# Connectors.net
KiCad netlist of a schematic drawn in Altium Designer
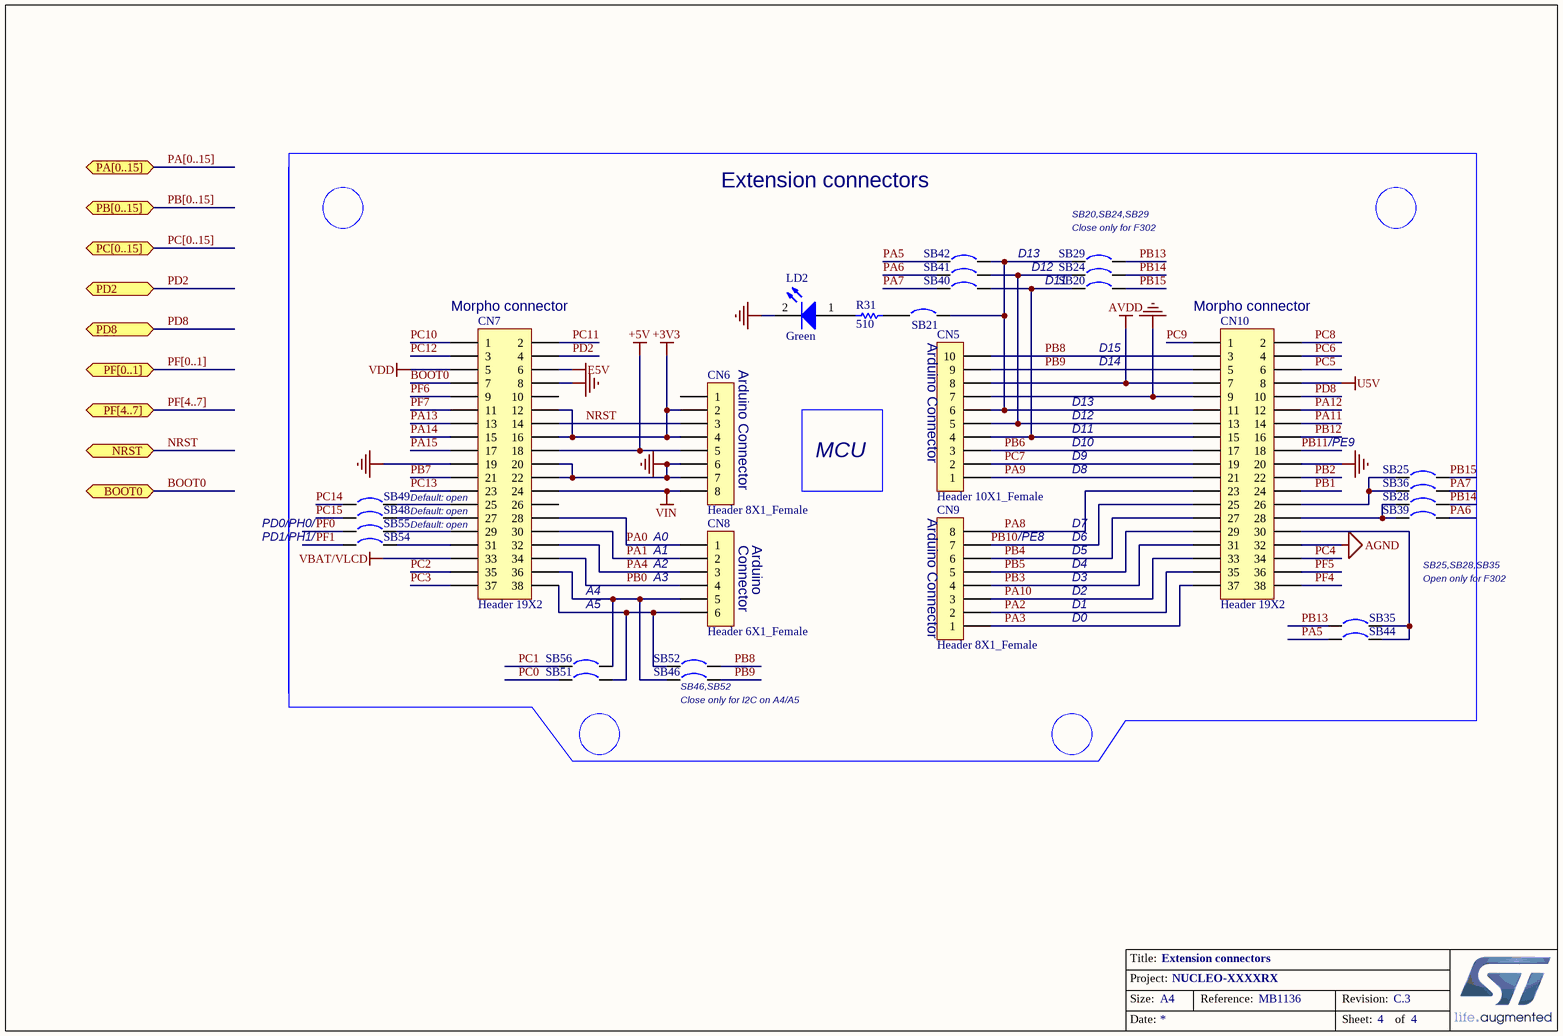
[diagram p0: Connectors.SchDoc]

(export (version "E")
  (design (tool "Eeschema 10.0.6"))
  (components
    (comp (ref "CN5")
      (value "Header 10X1_Female")
      (footprint "1*10P_FEMALE")
      (description "Header, 10-Pin, Single row,female")
      (fields (field (name "PUBLISHER") "Altium Limited"))
      (libsource (lib "Nucleo_64") (part "Header 10X1_Female"))
    )
    (comp (ref "CN6")
      (value "Header 8X1_Female")
      (footprint "1*8P_FEMALE")
      (description "Header, 8-Pin, Single row,female")
      (fields (field (name "PUBLISHER") "Altium Limited"))
      (libsource (lib "") (part "Header 8X1_Female_1"))
    )
    (comp (ref "CN7")
      (value "Header 19X2")
      (footprint "2*19P")
      (description "Header, 19-Pin, Dual row")
      (fields (field (name "PUBLISHER") "Altium Limited"))
      (libsource (lib "Nucleo_64_1") (part "Header 19X2"))
    )
    (comp (ref "CN8")
      (value "Header 6X1_Female")
      (footprint "1*6P_FEMALE")
      (description "Header, 6-Pin, Single row,female")
      (fields (field (name "PUBLISHER") "Altium Limited"))
      (libsource (lib "Nucleo_64") (part "Header 6X1_Female"))
    )
    (comp (ref "CN9")
      (value "Header 8X1_Female")
      (footprint "1*8P_FEMALE")
      (description "Header, 8-Pin, Single row,female")
      (fields (field (name "PUBLISHER") "Altium Limited"))
      (libsource (lib "Nucleo_64") (part "Header 8X1_Female"))
    )
    (comp (ref "CN10")
      (value "Header 19X2")
      (footprint "2*19P")
      (description "Header, 19-Pin, Dual row")
      (fields (field (name "PUBLISHER") "Altium Limited"))
      (libsource (lib "Nucleo_64_1") (part "Header 19X2"))
    )
    (comp (ref "LD2")
      (value "Green")
      (footprint "0603D")
      (description "Typical RED, GREEN, YELLOW, AMBER GaAs LED")
      (fields (field (name "PUBLISHER") "Altium Limited"))
      (libsource (lib "Miscellaneous Devices") (part "LED2"))
    )
    (comp (ref "R31")
      (value "510")
      (footprint "0603R")
      (description "Resistor")
      (fields (field (name "PUBLISHER") "Altium Limited"))
      (libsource (lib "Miscellaneous Devices") (part "Res1"))
    )
    (comp (ref "SB20")
      (value "Circuit Breaker")
      (footprint "JP2_SMD")
      (fields (field (name "PUBLISHER") "Altium Limited"))
      (libsource (lib "") (part "Circuit Breaker_1"))
    )
    (comp (ref "SB21")
      (value "Circuit Breaker")
      (footprint "JP2_SMD")
      (fields (field (name "PUBLISHER") "Altium Limited"))
      (libsource (lib "") (part "Circuit Breaker_1"))
    )
    (comp (ref "SB24")
      (value "Circuit Breaker")
      (footprint "JP2_SMD")
      (fields (field (name "PUBLISHER") "Altium Limited"))
      (libsource (lib "") (part "Circuit Breaker_1"))
    )
    (comp (ref "SB25")
      (value "Circuit Breaker")
      (footprint "JP2_SMD")
      (fields (field (name "PUBLISHER") "Altium Limited"))
      (libsource (lib "MCD_TOOLS") (part "Circuit Breaker"))
    )
    (comp (ref "SB28")
      (value "Circuit Breaker")
      (footprint "JP2_SMD")
      (fields (field (name "PUBLISHER") "Altium Limited"))
      (libsource (lib "MCD_TOOLS") (part "Circuit Breaker"))
    )
    (comp (ref "SB29")
      (value "Circuit Breaker")
      (footprint "JP2_SMD")
      (fields (field (name "PUBLISHER") "Altium Limited"))
      (libsource (lib "") (part "Circuit Breaker_1"))
    )
    (comp (ref "SB35")
      (value "Circuit Breaker")
      (footprint "JP2_SMD")
      (fields (field (name "PUBLISHER") "Altium Limited"))
      (libsource (lib "MCD_TOOLS") (part "Circuit Breaker"))
    )
    (comp (ref "SB36")
      (value "Circuit Breaker")
      (footprint "JP2_SMD")
      (fields (field (name "PUBLISHER") "Altium Limited"))
      (libsource (lib "MCD_TOOLS") (part "Circuit Breaker"))
    )
    (comp (ref "SB39")
      (value "Circuit Breaker")
      (footprint "JP2_SMD")
      (fields (field (name "PUBLISHER") "Altium Limited"))
      (libsource (lib "MCD_TOOLS") (part "Circuit Breaker"))
    )
    (comp (ref "SB40")
      (value "Circuit Breaker")
      (footprint "JP2_SMD")
      (fields (field (name "PUBLISHER") "Altium Limited"))
      (libsource (lib "") (part "Circuit Breaker_1"))
    )
    (comp (ref "SB41")
      (value "Circuit Breaker")
      (footprint "JP2_SMD")
      (fields (field (name "PUBLISHER") "Altium Limited"))
      (libsource (lib "") (part "Circuit Breaker_1"))
    )
    (comp (ref "SB42")
      (value "Circuit Breaker")
      (footprint "JP2_SMD")
      (fields (field (name "PUBLISHER") "Altium Limited"))
      (libsource (lib "") (part "Circuit Breaker_1"))
    )
    (comp (ref "SB44")
      (value "Circuit Breaker")
      (footprint "JP2_SMD")
      (fields (field (name "PUBLISHER") "Altium Limited"))
      (libsource (lib "MCD_TOOLS") (part "Circuit Breaker"))
    )
    (comp (ref "SB46")
      (value "Circuit Breaker")
      (footprint "JP2_SMD")
      (fields (field (name "PUBLISHER") "Altium Limited"))
      (libsource (lib "") (part "Circuit Breaker_1"))
    )
    (comp (ref "SB48")
      (value "Circuit Breaker")
      (footprint "JP2_SMD")
      (fields (field (name "PUBLISHER") "Altium Limited"))
      (libsource (lib "MCD_TOOLS") (part "Circuit Breaker"))
    )
    (comp (ref "SB49")
      (value "Circuit Breaker")
      (footprint "JP2_SMD")
      (fields (field (name "PUBLISHER") "Altium Limited"))
      (libsource (lib "MCD_TOOLS") (part "Circuit Breaker"))
    )
    (comp (ref "SB51")
      (value "Circuit Breaker")
      (footprint "JP2_SMD")
      (fields (field (name "PUBLISHER") "Altium Limited"))
      (libsource (lib "") (part "Circuit Breaker_1"))
    )
    (comp (ref "SB52")
      (value "Circuit Breaker")
      (footprint "JP2_SMD")
      (fields (field (name "PUBLISHER") "Altium Limited"))
      (libsource (lib "") (part "Circuit Breaker_1"))
    )
    (comp (ref "SB54")
      (value "Circuit Breaker")
      (footprint "JP2_SMD")
      (fields (field (name "PUBLISHER") "Altium Limited"))
      (libsource (lib "MCD_TOOLS") (part "Circuit Breaker"))
    )
    (comp (ref "SB55")
      (value "Circuit Breaker")
      (footprint "JP2_SMD")
      (fields (field (name "PUBLISHER") "Altium Limited"))
      (libsource (lib "MCD_TOOLS") (part "Circuit Breaker"))
    )
    (comp (ref "SB56")
      (value "Circuit Breaker")
      (footprint "JP2_SMD")
      (fields (field (name "PUBLISHER") "Altium Limited"))
      (libsource (lib "") (part "Circuit Breaker_1"))
    )
  )
  (nets
    (net (code "1") (name "+3V3") (class "Default")
      (node (ref "CN6") (pin "2") (pinfunction "2_2") (pintype "passive"))
      (node (ref "CN6") (pin "4") (pinfunction "4_4") (pintype "passive"))
      (node (ref "CN7") (pin "12") (pinfunction "12_12") (pintype "passive"))
      (node (ref "CN7") (pin "16") (pinfunction "16_16") (pintype "passive"))
    )
    (net (code "2") (name "+5V") (class "Default")
      (node (ref "CN6") (pin "5") (pinfunction "5_5") (pintype "passive"))
      (node (ref "CN7") (pin "18") (pinfunction "18_18") (pintype "passive"))
    )
    (net (code "3") (name "/BOOT0") (class "Default")
      (node (ref "CN7") (pin "7") (pinfunction "7_7") (pintype "passive"))
    )
    (net (code "4") (name "/NRST") (class "Default")
      (node (ref "CN6") (pin "3") (pinfunction "3_3") (pintype "passive"))
      (node (ref "CN7") (pin "14") (pinfunction "14_14") (pintype "passive"))
    )
    (net (code "5") (name "/PA0") (class "Default")
      (node (ref "CN7") (pin "28") (pinfunction "28_28") (pintype "passive"))
      (node (ref "CN8") (pin "1") (pinfunction "1_1") (pintype "passive"))
    )
    (net (code "6") (name "/PA1") (class "Default")
      (node (ref "CN7") (pin "30") (pinfunction "30_30") (pintype "passive"))
      (node (ref "CN8") (pin "2") (pinfunction "2_2") (pintype "passive"))
    )
    (net (code "7") (name "/PA2") (class "Default")
      (node (ref "CN10") (pin "35") (pinfunction "35_35") (pintype "passive"))
      (node (ref "CN9") (pin "2") (pinfunction "2_2") (pintype "passive"))
    )
    (net (code "8") (name "/PA3") (class "Default")
      (node (ref "CN10") (pin "37") (pinfunction "37_37") (pintype "passive"))
      (node (ref "CN9") (pin "1") (pinfunction "1_1") (pintype "passive"))
    )
    (net (code "9") (name "/PA4") (class "Default")
      (node (ref "CN7") (pin "32") (pinfunction "32_32") (pintype "passive"))
      (node (ref "CN8") (pin "3") (pinfunction "3_3") (pintype "passive"))
    )
    (net (code "10") (name "/PA5") (class "Default")
      (node (ref "SB42") (pin "1") (pinfunction "1_1") (pintype "passive"))
      (node (ref "SB44") (pin "2") (pinfunction "2_2") (pintype "passive"))
    )
    (net (code "11") (name "/PA6") (class "Default")
      (node (ref "SB39") (pin "1") (pinfunction "1_1") (pintype "passive"))
      (node (ref "SB41") (pin "1") (pinfunction "1_1") (pintype "passive"))
    )
    (net (code "12") (name "/PA7") (class "Default")
      (node (ref "SB36") (pin "1") (pinfunction "1_1") (pintype "passive"))
      (node (ref "SB40") (pin "1") (pinfunction "1_1") (pintype "passive"))
    )
    (net (code "13") (name "/PA8") (class "Default")
      (node (ref "CN10") (pin "23") (pinfunction "23_23") (pintype "passive"))
      (node (ref "CN9") (pin "8") (pinfunction "8_8") (pintype "passive"))
    )
    (net (code "14") (name "/PA9") (class "Default")
      (node (ref "CN10") (pin "21") (pinfunction "21_21") (pintype "passive"))
      (node (ref "CN5") (pin "1") (pinfunction "1_1") (pintype "passive"))
    )
    (net (code "15") (name "/PA10") (class "Default")
      (node (ref "CN10") (pin "33") (pinfunction "33_33") (pintype "passive"))
      (node (ref "CN9") (pin "3") (pinfunction "3_3") (pintype "passive"))
    )
    (net (code "16") (name "/PA11") (class "Default")
      (node (ref "CN10") (pin "14") (pinfunction "14_14") (pintype "passive"))
    )
    (net (code "17") (name "/PA12") (class "Default")
      (node (ref "CN10") (pin "12") (pinfunction "12_12") (pintype "passive"))
    )
    (net (code "18") (name "/PA13") (class "Default")
      (node (ref "CN7") (pin "13") (pinfunction "13_13") (pintype "passive"))
    )
    (net (code "19") (name "/PA14") (class "Default")
      (node (ref "CN7") (pin "15") (pinfunction "15_15") (pintype "passive"))
    )
    (net (code "20") (name "/PA15") (class "Default")
      (node (ref "CN7") (pin "17") (pinfunction "17_17") (pintype "passive"))
    )
    (net (code "22") (name "/PB0") (class "Default")
      (node (ref "CN7") (pin "34") (pinfunction "34_34") (pintype "passive"))
      (node (ref "CN8") (pin "4") (pinfunction "4_4") (pintype "passive"))
    )
    (net (code "23") (name "/PB1") (class "Default")
      (node (ref "CN10") (pin "24") (pinfunction "24_24") (pintype "passive"))
    )
    (net (code "24") (name "/PB2") (class "Default")
      (node (ref "CN10") (pin "22") (pinfunction "22_22") (pintype "passive"))
    )
    (net (code "25") (name "/PB3") (class "Default")
      (node (ref "CN10") (pin "31") (pinfunction "31_31") (pintype "passive"))
      (node (ref "CN9") (pin "4") (pinfunction "4_4") (pintype "passive"))
    )
    (net (code "26") (name "/PB4") (class "Default")
      (node (ref "CN10") (pin "27") (pinfunction "27_27") (pintype "passive"))
      (node (ref "CN9") (pin "6") (pinfunction "6_6") (pintype "passive"))
    )
    (net (code "27") (name "/PB5") (class "Default")
      (node (ref "CN10") (pin "29") (pinfunction "29_29") (pintype "passive"))
      (node (ref "CN9") (pin "5") (pinfunction "5_5") (pintype "passive"))
    )
    (net (code "28") (name "/PB6") (class "Default")
      (node (ref "CN10") (pin "17") (pinfunction "17_17") (pintype "passive"))
      (node (ref "CN5") (pin "3") (pinfunction "3_3") (pintype "passive"))
    )
    (net (code "29") (name "/PB7") (class "Default")
      (node (ref "CN7") (pin "21") (pinfunction "21_21") (pintype "passive"))
    )
    (net (code "30") (name "/PB8") (class "Default")
      (node (ref "CN10") (pin "3") (pinfunction "3_3") (pintype "passive"))
      (node (ref "CN5") (pin "10") (pinfunction "10_10") (pintype "passive"))
      (node (ref "SB52") (pin "2") (pinfunction "2_2") (pintype "passive"))
    )
    (net (code "31") (name "/PB9") (class "Default")
      (node (ref "CN10") (pin "5") (pinfunction "5_5") (pintype "passive"))
      (node (ref "CN5") (pin "9") (pinfunction "9_9") (pintype "passive"))
      (node (ref "SB46") (pin "2") (pinfunction "2_2") (pintype "passive"))
    )
    (net (code "32") (name "/PB10") (class "Default")
      (node (ref "CN10") (pin "25") (pinfunction "25_25") (pintype "passive"))
      (node (ref "CN9") (pin "7") (pinfunction "7_7") (pintype "passive"))
    )
    (net (code "33") (name "/PB11") (class "Default")
      (node (ref "CN10") (pin "18") (pinfunction "18_18") (pintype "passive"))
    )
    (net (code "34") (name "/PB12") (class "Default")
      (node (ref "CN10") (pin "16") (pinfunction "16_16") (pintype "passive"))
    )
    (net (code "35") (name "/PB13") (class "Default")
      (node (ref "SB29") (pin "2") (pinfunction "2_2") (pintype "passive"))
      (node (ref "SB35") (pin "2") (pinfunction "2_2") (pintype "passive"))
    )
    (net (code "36") (name "/PB14") (class "Default")
      (node (ref "SB24") (pin "2") (pinfunction "2_2") (pintype "passive"))
      (node (ref "SB28") (pin "1") (pinfunction "1_1") (pintype "passive"))
    )
    (net (code "37") (name "/PB15") (class "Default")
      (node (ref "SB20") (pin "2") (pinfunction "2_2") (pintype "passive"))
      (node (ref "SB25") (pin "1") (pinfunction "1_1") (pintype "passive"))
    )
    (net (code "39") (name "/PC0") (class "Default")
      (node (ref "SB51") (pin "1") (pinfunction "1_1") (pintype "passive"))
    )
    (net (code "40") (name "/PC1") (class "Default")
      (node (ref "SB56") (pin "1") (pinfunction "1_1") (pintype "passive"))
    )
    (net (code "41") (name "/PC2") (class "Default")
      (node (ref "CN7") (pin "35") (pinfunction "35_35") (pintype "passive"))
    )
    (net (code "42") (name "/PC3") (class "Default")
      (node (ref "CN7") (pin "37") (pinfunction "37_37") (pintype "passive"))
    )
    (net (code "43") (name "/PC4") (class "Default")
      (node (ref "CN10") (pin "34") (pinfunction "34_34") (pintype "passive"))
    )
    (net (code "44") (name "/PC5") (class "Default")
      (node (ref "CN10") (pin "6") (pinfunction "6_6") (pintype "passive"))
    )
    (net (code "45") (name "/PC6") (class "Default")
      (node (ref "CN10") (pin "4") (pinfunction "4_4") (pintype "passive"))
    )
    (net (code "46") (name "/PC7") (class "Default")
      (node (ref "CN10") (pin "19") (pinfunction "19_19") (pintype "passive"))
      (node (ref "CN5") (pin "2") (pinfunction "2_2") (pintype "passive"))
    )
    (net (code "47") (name "/PC8") (class "Default")
      (node (ref "CN10") (pin "2") (pinfunction "2_2") (pintype "passive"))
    )
    (net (code "48") (name "/PC9") (class "Default")
      (node (ref "CN10") (pin "1") (pinfunction "1_1") (pintype "passive"))
    )
    (net (code "49") (name "/PC10") (class "Default")
      (node (ref "CN7") (pin "1") (pinfunction "1_1") (pintype "passive"))
    )
    (net (code "50") (name "/PC11") (class "Default")
      (node (ref "CN7") (pin "2") (pinfunction "2_2") (pintype "passive"))
    )
    (net (code "51") (name "/PC12") (class "Default")
      (node (ref "CN7") (pin "3") (pinfunction "3_3") (pintype "passive"))
    )
    (net (code "52") (name "/PC13") (class "Default")
      (node (ref "CN7") (pin "23") (pinfunction "23_23") (pintype "passive"))
    )
    (net (code "53") (name "/PC14") (class "Default")
      (node (ref "SB49") (pin "2") (pinfunction "2_2") (pintype "passive"))
    )
    (net (code "54") (name "/PC15") (class "Default")
      (node (ref "SB48") (pin "2") (pinfunction "2_2") (pintype "passive"))
    )
    (net (code "56") (name "/PD2") (class "Default")
      (node (ref "CN7") (pin "4") (pinfunction "4_4") (pintype "passive"))
    )
    (net (code "57") (name "/PD8") (class "Default")
      (node (ref "CN10") (pin "10") (pinfunction "10_10") (pintype "passive"))
    )
    (net (code "58") (name "/PF0") (class "Default")
      (node (ref "SB55") (pin "2") (pinfunction "2_2") (pintype "passive"))
    )
    (net (code "59") (name "/PF1") (class "Default")
      (node (ref "SB54") (pin "2") (pinfunction "2_2") (pintype "passive"))
    )
    (net (code "60") (name "/PF4") (class "Default")
      (node (ref "CN10") (pin "38") (pinfunction "38_38") (pintype "passive"))
    )
    (net (code "61") (name "/PF5") (class "Default")
      (node (ref "CN10") (pin "36") (pinfunction "36_36") (pintype "passive"))
    )
    (net (code "62") (name "/PF6") (class "Default")
      (node (ref "CN7") (pin "9") (pinfunction "9_9") (pintype "passive"))
    )
    (net (code "63") (name "/PF7") (class "Default")
      (node (ref "CN7") (pin "11") (pinfunction "11_11") (pintype "passive"))
    )
    (net (code "66") (name "AGND") (class "Default")
      (node (ref "CN10") (pin "32") (pinfunction "32_32") (pintype "passive"))
    )
    (net (code "67") (name "AVDD") (class "Default")
      (node (ref "CN10") (pin "7") (pinfunction "7_7") (pintype "passive"))
      (node (ref "CN5") (pin "8") (pinfunction "8_8") (pintype "passive"))
    )
    (net (code "68") (name "E5V") (class "Default")
      (node (ref "CN7") (pin "6") (pinfunction "6_6") (pintype "passive"))
    )
    (net (code "69") (name "GND") (class "Default")
      (node (ref "CN10") (pin "20") (pinfunction "20_20") (pintype "passive"))
      (node (ref "CN10") (pin "9") (pinfunction "9_9") (pintype "passive"))
      (node (ref "CN5") (pin "7") (pinfunction "7_7") (pintype "passive"))
      (node (ref "CN6") (pin "6") (pinfunction "6_6") (pintype "passive"))
      (node (ref "CN6") (pin "7") (pinfunction "7_7") (pintype "passive"))
      (node (ref "CN7") (pin "19") (pinfunction "19_19") (pintype "passive"))
      (node (ref "CN7") (pin "20") (pinfunction "20_20") (pintype "passive"))
      (node (ref "CN7") (pin "22") (pinfunction "22_22") (pintype "passive"))
      (node (ref "CN7") (pin "8") (pinfunction "8_8") (pintype "passive"))
      (node (ref "LD2") (pin "2") (pinfunction "K_2") (pintype "passive"))
    )
    (net (code "70") (name "Net-(CN7-Pad25)") (class "Default")
      (node (ref "CN7") (pin "25") (pinfunction "25_25") (pintype "passive"))
      (node (ref "SB49") (pin "1") (pinfunction "1_1") (pintype "passive"))
    )
    (net (code "71") (name "Net-(CN7-Pad27)") (class "Default")
      (node (ref "CN7") (pin "27") (pinfunction "27_27") (pintype "passive"))
      (node (ref "SB48") (pin "1") (pinfunction "1_1") (pintype "passive"))
    )
    (net (code "72") (name "Net-(CN7-Pad29)") (class "Default")
      (node (ref "CN7") (pin "29") (pinfunction "29_29") (pintype "passive"))
      (node (ref "SB55") (pin "1") (pinfunction "1_1") (pintype "passive"))
    )
    (net (code "73") (name "Net-(CN7-Pad31)") (class "Default")
      (node (ref "CN7") (pin "31") (pinfunction "31_31") (pintype "passive"))
      (node (ref "SB54") (pin "1") (pinfunction "1_1") (pintype "passive"))
    )
    (net (code "74") (name "Net-(CN7-Pad36)") (class "Default")
      (node (ref "CN7") (pin "36") (pinfunction "36_36") (pintype "passive"))
      (node (ref "CN8") (pin "5") (pinfunction "5_5") (pintype "passive"))
      (node (ref "SB46") (pin "1") (pinfunction "1_1") (pintype "passive"))
      (node (ref "SB56") (pin "2") (pinfunction "2_2") (pintype "passive"))
    )
    (net (code "75") (name "Net-(CN7-Pad38)") (class "Default")
      (node (ref "CN7") (pin "38") (pinfunction "38_38") (pintype "passive"))
      (node (ref "CN8") (pin "6") (pinfunction "6_6") (pintype "passive"))
      (node (ref "SB51") (pin "2") (pinfunction "2_2") (pintype "passive"))
      (node (ref "SB52") (pin "1") (pinfunction "1_1") (pintype "passive"))
    )
    (net (code "76") (name "Net-(CN10-Pad11)") (class "Default")
      (node (ref "CN10") (pin "11") (pinfunction "11_11") (pintype "passive"))
      (node (ref "CN5") (pin "6") (pinfunction "6_6") (pintype "passive"))
      (node (ref "SB21") (pin "2") (pinfunction "2_2") (pintype "passive"))
      (node (ref "SB29") (pin "1") (pinfunction "1_1") (pintype "passive"))
      (node (ref "SB42") (pin "2") (pinfunction "2_2") (pintype "passive"))
    )
    (net (code "77") (name "Net-(CN10-Pad13)") (class "Default")
      (node (ref "CN10") (pin "13") (pinfunction "13_13") (pintype "passive"))
      (node (ref "CN5") (pin "5") (pinfunction "5_5") (pintype "passive"))
      (node (ref "SB24") (pin "1") (pinfunction "1_1") (pintype "passive"))
      (node (ref "SB41") (pin "2") (pinfunction "2_2") (pintype "passive"))
    )
    (net (code "78") (name "Net-(CN10-Pad15)") (class "Default")
      (node (ref "CN10") (pin "15") (pinfunction "15_15") (pintype "passive"))
      (node (ref "CN5") (pin "4") (pinfunction "4_4") (pintype "passive"))
      (node (ref "SB20") (pin "1") (pinfunction "1_1") (pintype "passive"))
      (node (ref "SB40") (pin "2") (pinfunction "2_2") (pintype "passive"))
    )
    (net (code "79") (name "Net-(CN10-Pad26)") (class "Default")
      (node (ref "CN10") (pin "26") (pinfunction "26_26") (pintype "passive"))
      (node (ref "SB25") (pin "2") (pinfunction "2_2") (pintype "passive"))
      (node (ref "SB36") (pin "2") (pinfunction "2_2") (pintype "passive"))
    )
    (net (code "80") (name "Net-(CN10-Pad28)") (class "Default")
      (node (ref "CN10") (pin "28") (pinfunction "28_28") (pintype "passive"))
      (node (ref "SB28") (pin "2") (pinfunction "2_2") (pintype "passive"))
      (node (ref "SB39") (pin "2") (pinfunction "2_2") (pintype "passive"))
    )
    (net (code "81") (name "Net-(CN10-Pad30)") (class "Default")
      (node (ref "CN10") (pin "30") (pinfunction "30_30") (pintype "passive"))
      (node (ref "SB35") (pin "1") (pinfunction "1_1") (pintype "passive"))
      (node (ref "SB44") (pin "1") (pinfunction "1_1") (pintype "passive"))
    )
    (net (code "82") (name "Net-(LD2-A)") (class "Default")
      (node (ref "LD2") (pin "1") (pinfunction "A_1") (pintype "passive"))
      (node (ref "R31") (pin "2") (pinfunction "2_2") (pintype "passive"))
    )
    (net (code "83") (name "Net-(R31-Pad1)") (class "Default")
      (node (ref "R31") (pin "1") (pinfunction "1_1") (pintype "passive"))
      (node (ref "SB21") (pin "1") (pinfunction "1_1") (pintype "passive"))
    )
    (net (code "84") (name "U5V") (class "Default")
      (node (ref "CN10") (pin "8") (pinfunction "8_8") (pintype "passive"))
    )
    (net (code "85") (name "VBAT{slash}VLCD") (class "Default")
      (node (ref "CN7") (pin "33") (pinfunction "33_33") (pintype "passive"))
    )
    (net (code "86") (name "VDD") (class "Default")
      (node (ref "CN7") (pin "5") (pinfunction "5_5") (pintype "passive"))
    )
    (net (code "87") (name "VIN") (class "Default")
      (node (ref "CN6") (pin "8") (pinfunction "8_8") (pintype "passive"))
      (node (ref "CN7") (pin "24") (pinfunction "24_24") (pintype "passive"))
    )
    (net (code "88") (name "unconnected-(CN6-Pad1)") (class "Default")
      (node (ref "CN6") (pin "1") (pinfunction "1_1") (pintype "passive"))
    )
    (net (code "89") (name "unconnected-(CN7-Pad10)") (class "Default")
      (node (ref "CN7") (pin "10") (pinfunction "10_10") (pintype "passive"))
    )
    (net (code "90") (name "unconnected-(CN7-Pad26)") (class "Default")
      (node (ref "CN7") (pin "26") (pinfunction "26_26") (pintype "passive"))
    )
  )
)
